# Trepanat_Pressure.net
KiCad netlist of a schematic drawn in Altium Designer
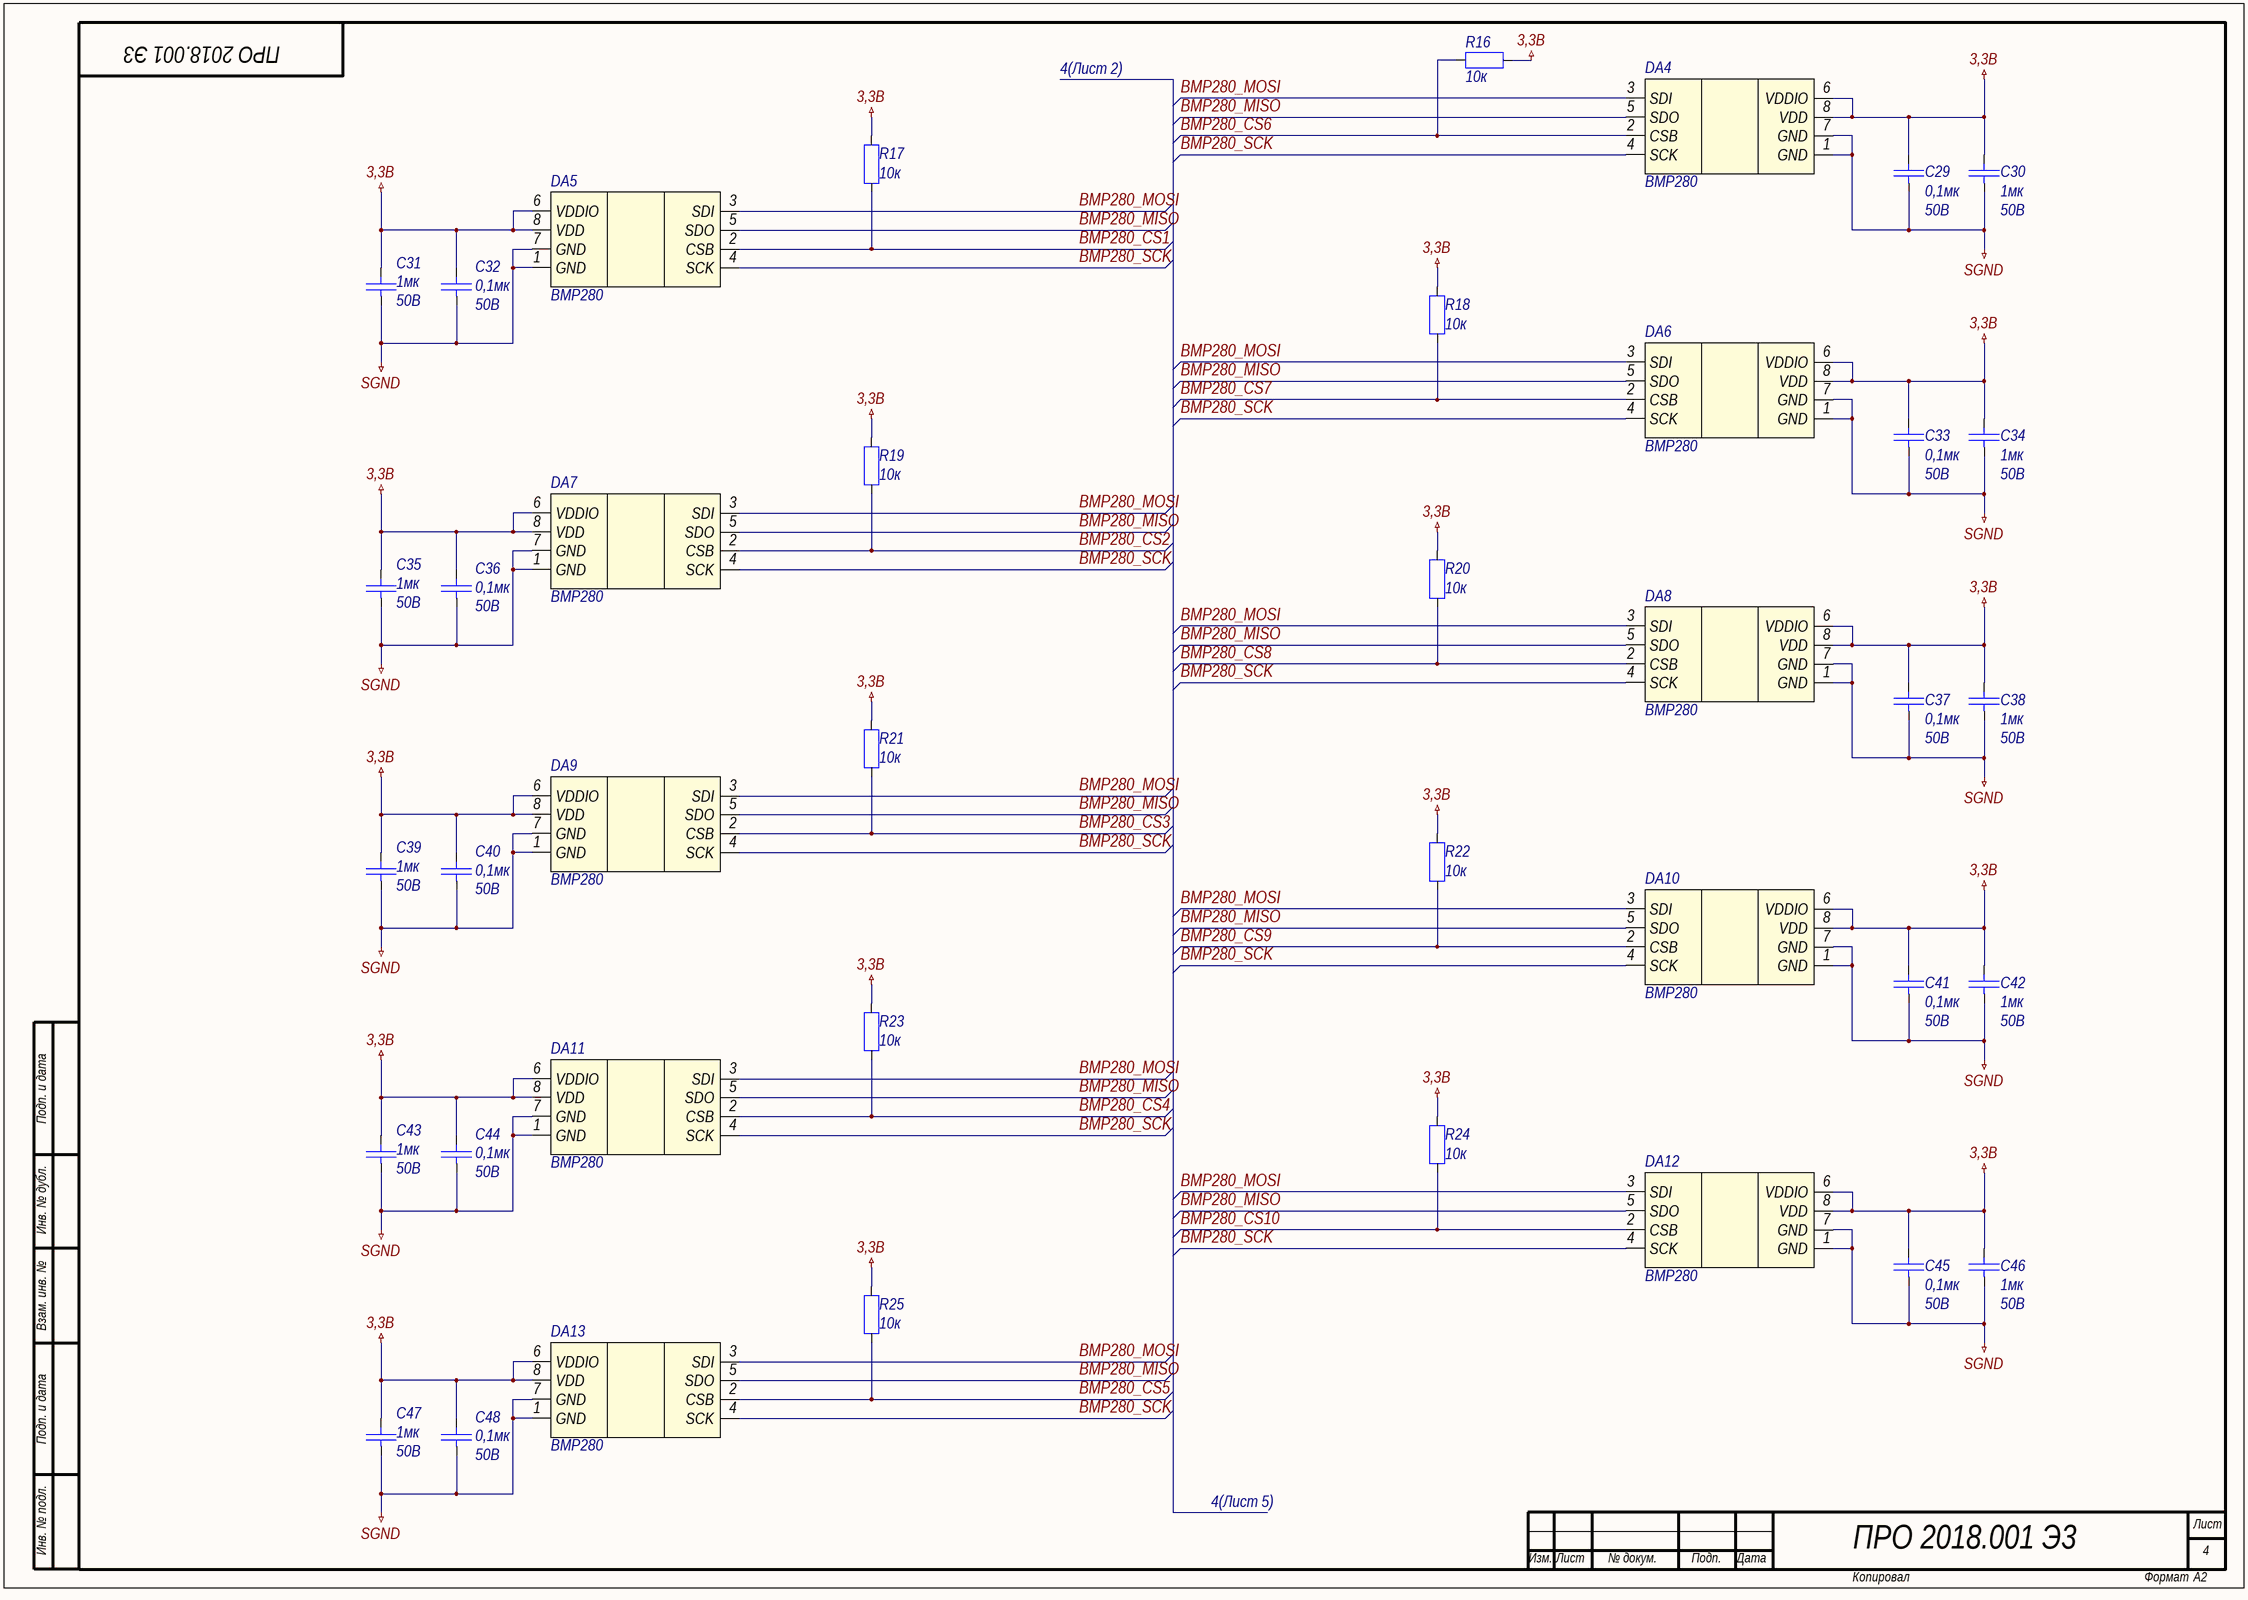
[diagram p0: Trepanat_Pressure.SchDoc]

(export (version "E")
  (design (tool "Eeschema 10.0.6"))
  (components
    (comp (ref "C29")
      (value "0,1мк")
      (footprint "ZabugorLib:C0805")
      (description "Конденсатор")
      (fields (field (name "VOLTAGE") "50В"))
      (libsource (lib "ZabugorLib") (part "Capacitor"))
    )
    (comp (ref "C30")
      (value "1мк")
      (footprint "ZabugorLib:C0805")
      (description "Конденсатор")
      (fields (field (name "VOLTAGE") "50В"))
      (libsource (lib "ZabugorLib") (part "Capacitor"))
    )
    (comp (ref "C31")
      (value "1мк")
      (footprint "ZabugorLib:C0805")
      (description "Конденсатор")
      (fields (field (name "VOLTAGE") "50В"))
      (libsource (lib "ZabugorLib") (part "Capacitor"))
    )
    (comp (ref "C32")
      (value "0,1мк")
      (footprint "ZabugorLib:C0805")
      (description "Конденсатор")
      (fields (field (name "VOLTAGE") "50В"))
      (libsource (lib "ZabugorLib") (part "Capacitor"))
    )
    (comp (ref "C33")
      (value "0,1мк")
      (footprint "ZabugorLib:C0805")
      (description "Конденсатор")
      (fields (field (name "VOLTAGE") "50В"))
      (libsource (lib "ZabugorLib") (part "Capacitor"))
    )
    (comp (ref "C34")
      (value "1мк")
      (footprint "ZabugorLib:C0805")
      (description "Конденсатор")
      (fields (field (name "VOLTAGE") "50В"))
      (libsource (lib "ZabugorLib") (part "Capacitor"))
    )
    (comp (ref "C35")
      (value "1мк")
      (footprint "ZabugorLib:C0805")
      (description "Конденсатор")
      (fields (field (name "VOLTAGE") "50В"))
      (libsource (lib "ZabugorLib") (part "Capacitor"))
    )
    (comp (ref "C36")
      (value "0,1мк")
      (footprint "ZabugorLib:C0805")
      (description "Конденсатор")
      (fields (field (name "VOLTAGE") "50В"))
      (libsource (lib "ZabugorLib") (part "Capacitor"))
    )
    (comp (ref "C37")
      (value "0,1мк")
      (footprint "ZabugorLib:C0805")
      (description "Конденсатор")
      (fields (field (name "VOLTAGE") "50В"))
      (libsource (lib "ZabugorLib") (part "Capacitor"))
    )
    (comp (ref "C38")
      (value "1мк")
      (footprint "ZabugorLib:C0805")
      (description "Конденсатор")
      (fields (field (name "VOLTAGE") "50В"))
      (libsource (lib "ZabugorLib") (part "Capacitor"))
    )
    (comp (ref "C39")
      (value "1мк")
      (footprint "ZabugorLib:C0805")
      (description "Конденсатор")
      (fields (field (name "VOLTAGE") "50В"))
      (libsource (lib "ZabugorLib") (part "Capacitor"))
    )
    (comp (ref "C40")
      (value "0,1мк")
      (footprint "ZabugorLib:C0805")
      (description "Конденсатор")
      (fields (field (name "VOLTAGE") "50В"))
      (libsource (lib "ZabugorLib") (part "Capacitor"))
    )
    (comp (ref "C41")
      (value "0,1мк")
      (footprint "ZabugorLib:C0805")
      (description "Конденсатор")
      (fields (field (name "VOLTAGE") "50В"))
      (libsource (lib "ZabugorLib") (part "Capacitor"))
    )
    (comp (ref "C42")
      (value "1мк")
      (footprint "ZabugorLib:C0805")
      (description "Конденсатор")
      (fields (field (name "VOLTAGE") "50В"))
      (libsource (lib "ZabugorLib") (part "Capacitor"))
    )
    (comp (ref "C43")
      (value "1мк")
      (footprint "ZabugorLib:C0805")
      (description "Конденсатор")
      (fields (field (name "VOLTAGE") "50В"))
      (libsource (lib "ZabugorLib") (part "Capacitor"))
    )
    (comp (ref "C44")
      (value "0,1мк")
      (footprint "ZabugorLib:C0805")
      (description "Конденсатор")
      (fields (field (name "VOLTAGE") "50В"))
      (libsource (lib "ZabugorLib") (part "Capacitor"))
    )
    (comp (ref "C45")
      (value "0,1мк")
      (footprint "ZabugorLib:C0805")
      (description "Конденсатор")
      (fields (field (name "VOLTAGE") "50В"))
      (libsource (lib "ZabugorLib") (part "Capacitor"))
    )
    (comp (ref "C46")
      (value "1мк")
      (footprint "ZabugorLib:C0805")
      (description "Конденсатор")
      (fields (field (name "VOLTAGE") "50В"))
      (libsource (lib "ZabugorLib") (part "Capacitor"))
    )
    (comp (ref "C47")
      (value "1мк")
      (footprint "ZabugorLib:C0805")
      (description "Конденсатор")
      (fields (field (name "VOLTAGE") "50В"))
      (libsource (lib "ZabugorLib") (part "Capacitor"))
    )
    (comp (ref "C48")
      (value "0,1мк")
      (footprint "ZabugorLib:C0805")
      (description "Конденсатор")
      (fields (field (name "VOLTAGE") "50В"))
      (libsource (lib "ZabugorLib") (part "Capacitor"))
    )
    (comp (ref "DA4")
      (value "BMP280")
      (footprint "ZabugorLib:BMP280")
      (description "BMP280 Barometric Sensor")
      (libsource (lib "") (part "BMP280_1"))
    )
    (comp (ref "DA5")
      (value "BMP280")
      (footprint "ZabugorLib:BMP280")
      (description "BMP280 Barometric Sensor")
      (libsource (lib "ZabugorLib") (part "BMP280"))
    )
    (comp (ref "DA6")
      (value "BMP280")
      (footprint "ZabugorLib:BMP280")
      (description "BMP280 Barometric Sensor")
      (libsource (lib "") (part "BMP280_1"))
    )
    (comp (ref "DA7")
      (value "BMP280")
      (footprint "ZabugorLib:BMP280")
      (description "BMP280 Barometric Sensor")
      (libsource (lib "ZabugorLib") (part "BMP280"))
    )
    (comp (ref "DA8")
      (value "BMP280")
      (footprint "ZabugorLib:BMP280")
      (description "BMP280 Barometric Sensor")
      (libsource (lib "") (part "BMP280_1"))
    )
    (comp (ref "DA9")
      (value "BMP280")
      (footprint "ZabugorLib:BMP280")
      (description "BMP280 Barometric Sensor")
      (libsource (lib "ZabugorLib") (part "BMP280"))
    )
    (comp (ref "DA10")
      (value "BMP280")
      (footprint "ZabugorLib:BMP280")
      (description "BMP280 Barometric Sensor")
      (libsource (lib "") (part "BMP280_1"))
    )
    (comp (ref "DA11")
      (value "BMP280")
      (footprint "ZabugorLib:BMP280")
      (description "BMP280 Barometric Sensor")
      (libsource (lib "ZabugorLib") (part "BMP280"))
    )
    (comp (ref "DA12")
      (value "BMP280")
      (footprint "ZabugorLib:BMP280")
      (description "BMP280 Barometric Sensor")
      (libsource (lib "") (part "BMP280_1"))
    )
    (comp (ref "DA13")
      (value "BMP280")
      (footprint "ZabugorLib:BMP280")
      (description "BMP280 Barometric Sensor")
      (libsource (lib "ZabugorLib") (part "BMP280"))
    )
    (comp (ref "R16")
      (value "10к")
      (footprint "ZabugorLib:R0805")
      (description "Резистор")
      (libsource (lib "") (part "Resistor_1"))
    )
    (comp (ref "R17")
      (value "10к")
      (footprint "ZabugorLib:R0805")
      (description "Резистор")
      (libsource (lib "ZabugorLib") (part "Resistor"))
    )
    (comp (ref "R18")
      (value "10к")
      (footprint "ZabugorLib:R0805")
      (description "Резистор")
      (libsource (lib "ZabugorLib") (part "Resistor"))
    )
    (comp (ref "R19")
      (value "10к")
      (footprint "ZabugorLib:R0805")
      (description "Резистор")
      (libsource (lib "ZabugorLib") (part "Resistor"))
    )
    (comp (ref "R20")
      (value "10к")
      (footprint "ZabugorLib:R0805")
      (description "Резистор")
      (libsource (lib "ZabugorLib") (part "Resistor"))
    )
    (comp (ref "R21")
      (value "10к")
      (footprint "ZabugorLib:R0805")
      (description "Резистор")
      (libsource (lib "ZabugorLib") (part "Resistor"))
    )
    (comp (ref "R22")
      (value "10к")
      (footprint "ZabugorLib:R0805")
      (description "Резистор")
      (libsource (lib "ZabugorLib") (part "Resistor"))
    )
    (comp (ref "R23")
      (value "10к")
      (footprint "ZabugorLib:R0805")
      (description "Резистор")
      (libsource (lib "ZabugorLib") (part "Resistor"))
    )
    (comp (ref "R24")
      (value "10к")
      (footprint "ZabugorLib:R0805")
      (description "Резистор")
      (libsource (lib "ZabugorLib") (part "Resistor"))
    )
    (comp (ref "R25")
      (value "10к")
      (footprint "ZabugorLib:R0805")
      (description "Резистор")
      (libsource (lib "ZabugorLib") (part "Resistor"))
    )
  )
  (nets
    (net (code "1") (name "/BMP280_CS1") (class "Default")
      (node (ref "DA5") (pin "2") (pinfunction "CSB_2") (pintype "power_in"))
      (node (ref "R17") (pin "2") (pinfunction "2_2") (pintype "passive"))
    )
    (net (code "2") (name "/BMP280_CS2") (class "Default")
      (node (ref "DA7") (pin "2") (pinfunction "CSB_2") (pintype "power_in"))
      (node (ref "R19") (pin "2") (pinfunction "2_2") (pintype "passive"))
    )
    (net (code "3") (name "/BMP280_CS3") (class "Default")
      (node (ref "DA9") (pin "2") (pinfunction "CSB_2") (pintype "power_in"))
      (node (ref "R21") (pin "2") (pinfunction "2_2") (pintype "passive"))
    )
    (net (code "4") (name "/BMP280_CS4") (class "Default")
      (node (ref "DA11") (pin "2") (pinfunction "CSB_2") (pintype "power_in"))
      (node (ref "R23") (pin "2") (pinfunction "2_2") (pintype "passive"))
    )
    (net (code "5") (name "/BMP280_CS5") (class "Default")
      (node (ref "DA13") (pin "2") (pinfunction "CSB_2") (pintype "power_in"))
      (node (ref "R25") (pin "2") (pinfunction "2_2") (pintype "passive"))
    )
    (net (code "6") (name "/BMP280_CS6") (class "Default")
      (node (ref "DA4") (pin "2") (pinfunction "CSB_2") (pintype "power_in"))
      (node (ref "R16") (pin "2") (pinfunction "2_2") (pintype "passive"))
    )
    (net (code "7") (name "/BMP280_CS7") (class "Default")
      (node (ref "DA6") (pin "2") (pinfunction "CSB_2") (pintype "power_in"))
      (node (ref "R18") (pin "2") (pinfunction "2_2") (pintype "passive"))
    )
    (net (code "8") (name "/BMP280_CS8") (class "Default")
      (node (ref "DA8") (pin "2") (pinfunction "CSB_2") (pintype "power_in"))
      (node (ref "R20") (pin "2") (pinfunction "2_2") (pintype "passive"))
    )
    (net (code "9") (name "/BMP280_CS9") (class "Default")
      (node (ref "DA10") (pin "2") (pinfunction "CSB_2") (pintype "power_in"))
      (node (ref "R22") (pin "2") (pinfunction "2_2") (pintype "passive"))
    )
    (net (code "10") (name "/BMP280_CS10") (class "Default")
      (node (ref "DA12") (pin "2") (pinfunction "CSB_2") (pintype "power_in"))
      (node (ref "R24") (pin "2") (pinfunction "2_2") (pintype "passive"))
    )
    (net (code "11") (name "/BMP280_MISO") (class "Default")
      (node (ref "DA10") (pin "5") (pinfunction "SDO_5") (pintype "power_in"))
      (node (ref "DA11") (pin "5") (pinfunction "SDO_5") (pintype "power_in"))
      (node (ref "DA12") (pin "5") (pinfunction "SDO_5") (pintype "power_in"))
      (node (ref "DA13") (pin "5") (pinfunction "SDO_5") (pintype "power_in"))
      (node (ref "DA4") (pin "5") (pinfunction "SDO_5") (pintype "power_in"))
      (node (ref "DA5") (pin "5") (pinfunction "SDO_5") (pintype "power_in"))
      (node (ref "DA6") (pin "5") (pinfunction "SDO_5") (pintype "power_in"))
      (node (ref "DA7") (pin "5") (pinfunction "SDO_5") (pintype "power_in"))
      (node (ref "DA8") (pin "5") (pinfunction "SDO_5") (pintype "power_in"))
      (node (ref "DA9") (pin "5") (pinfunction "SDO_5") (pintype "power_in"))
    )
    (net (code "12") (name "/BMP280_MOSI") (class "Default")
      (node (ref "DA10") (pin "3") (pinfunction "SDI_3") (pintype "power_in"))
      (node (ref "DA11") (pin "3") (pinfunction "SDI_3") (pintype "power_in"))
      (node (ref "DA12") (pin "3") (pinfunction "SDI_3") (pintype "power_in"))
      (node (ref "DA13") (pin "3") (pinfunction "SDI_3") (pintype "power_in"))
      (node (ref "DA4") (pin "3") (pinfunction "SDI_3") (pintype "power_in"))
      (node (ref "DA5") (pin "3") (pinfunction "SDI_3") (pintype "power_in"))
      (node (ref "DA6") (pin "3") (pinfunction "SDI_3") (pintype "power_in"))
      (node (ref "DA7") (pin "3") (pinfunction "SDI_3") (pintype "power_in"))
      (node (ref "DA8") (pin "3") (pinfunction "SDI_3") (pintype "power_in"))
      (node (ref "DA9") (pin "3") (pinfunction "SDI_3") (pintype "power_in"))
    )
    (net (code "13") (name "/BMP280_SCK") (class "Default")
      (node (ref "DA10") (pin "4") (pinfunction "SCK_4") (pintype "power_in"))
      (node (ref "DA11") (pin "4") (pinfunction "SCK_4") (pintype "power_in"))
      (node (ref "DA12") (pin "4") (pinfunction "SCK_4") (pintype "power_in"))
      (node (ref "DA13") (pin "4") (pinfunction "SCK_4") (pintype "power_in"))
      (node (ref "DA4") (pin "4") (pinfunction "SCK_4") (pintype "power_in"))
      (node (ref "DA5") (pin "4") (pinfunction "SCK_4") (pintype "power_in"))
      (node (ref "DA6") (pin "4") (pinfunction "SCK_4") (pintype "power_in"))
      (node (ref "DA7") (pin "4") (pinfunction "SCK_4") (pintype "power_in"))
      (node (ref "DA8") (pin "4") (pinfunction "SCK_4") (pintype "power_in"))
      (node (ref "DA9") (pin "4") (pinfunction "SCK_4") (pintype "power_in"))
    )
    (net (code "14") (name "3,3B") (class "Default")
      (node (ref "C29") (pin "2") (pinfunction "2_2") (pintype "passive"))
      (node (ref "C30") (pin "2") (pinfunction "2_2") (pintype "passive"))
      (node (ref "C31") (pin "2") (pinfunction "2_2") (pintype "passive"))
      (node (ref "C32") (pin "2") (pinfunction "2_2") (pintype "passive"))
      (node (ref "C33") (pin "2") (pinfunction "2_2") (pintype "passive"))
      (node (ref "C34") (pin "2") (pinfunction "2_2") (pintype "passive"))
      (node (ref "C35") (pin "2") (pinfunction "2_2") (pintype "passive"))
      (node (ref "C36") (pin "2") (pinfunction "2_2") (pintype "passive"))
      (node (ref "C37") (pin "2") (pinfunction "2_2") (pintype "passive"))
      (node (ref "C38") (pin "2") (pinfunction "2_2") (pintype "passive"))
      (node (ref "C39") (pin "2") (pinfunction "2_2") (pintype "passive"))
      (node (ref "C40") (pin "2") (pinfunction "2_2") (pintype "passive"))
      (node (ref "C41") (pin "2") (pinfunction "2_2") (pintype "passive"))
      (node (ref "C42") (pin "2") (pinfunction "2_2") (pintype "passive"))
      (node (ref "C43") (pin "2") (pinfunction "2_2") (pintype "passive"))
      (node (ref "C44") (pin "2") (pinfunction "2_2") (pintype "passive"))
      (node (ref "C45") (pin "2") (pinfunction "2_2") (pintype "passive"))
      (node (ref "C46") (pin "2") (pinfunction "2_2") (pintype "passive"))
      (node (ref "C47") (pin "2") (pinfunction "2_2") (pintype "passive"))
      (node (ref "C48") (pin "2") (pinfunction "2_2") (pintype "passive"))
      (node (ref "DA10") (pin "6") (pinfunction "VDDIO_6") (pintype "power_in"))
      (node (ref "DA10") (pin "8") (pinfunction "VDD_8") (pintype "power_in"))
      (node (ref "DA11") (pin "6") (pinfunction "VDDIO_6") (pintype "power_in"))
      (node (ref "DA11") (pin "8") (pinfunction "VDD_8") (pintype "power_in"))
      (node (ref "DA12") (pin "6") (pinfunction "VDDIO_6") (pintype "power_in"))
      (node (ref "DA12") (pin "8") (pinfunction "VDD_8") (pintype "power_in"))
      (node (ref "DA13") (pin "6") (pinfunction "VDDIO_6") (pintype "power_in"))
      (node (ref "DA13") (pin "8") (pinfunction "VDD_8") (pintype "power_in"))
      (node (ref "DA4") (pin "6") (pinfunction "VDDIO_6") (pintype "power_in"))
      (node (ref "DA4") (pin "8") (pinfunction "VDD_8") (pintype "power_in"))
      (node (ref "DA5") (pin "6") (pinfunction "VDDIO_6") (pintype "power_in"))
      (node (ref "DA5") (pin "8") (pinfunction "VDD_8") (pintype "power_in"))
      (node (ref "DA6") (pin "6") (pinfunction "VDDIO_6") (pintype "power_in"))
      (node (ref "DA6") (pin "8") (pinfunction "VDD_8") (pintype "power_in"))
      (node (ref "DA7") (pin "6") (pinfunction "VDDIO_6") (pintype "power_in"))
      (node (ref "DA7") (pin "8") (pinfunction "VDD_8") (pintype "power_in"))
      (node (ref "DA8") (pin "6") (pinfunction "VDDIO_6") (pintype "power_in"))
      (node (ref "DA8") (pin "8") (pinfunction "VDD_8") (pintype "power_in"))
      (node (ref "DA9") (pin "6") (pinfunction "VDDIO_6") (pintype "power_in"))
      (node (ref "DA9") (pin "8") (pinfunction "VDD_8") (pintype "power_in"))
      (node (ref "R16") (pin "1") (pinfunction "1_1") (pintype "passive"))
      (node (ref "R17") (pin "1") (pinfunction "1_1") (pintype "passive"))
      (node (ref "R18") (pin "1") (pinfunction "1_1") (pintype "passive"))
      (node (ref "R19") (pin "1") (pinfunction "1_1") (pintype "passive"))
      (node (ref "R20") (pin "1") (pinfunction "1_1") (pintype "passive"))
      (node (ref "R21") (pin "1") (pinfunction "1_1") (pintype "passive"))
      (node (ref "R22") (pin "1") (pinfunction "1_1") (pintype "passive"))
      (node (ref "R23") (pin "1") (pinfunction "1_1") (pintype "passive"))
      (node (ref "R24") (pin "1") (pinfunction "1_1") (pintype "passive"))
      (node (ref "R25") (pin "1") (pinfunction "1_1") (pintype "passive"))
    )
    (net (code "15") (name "SGND") (class "Default")
      (node (ref "C29") (pin "1") (pinfunction "1_1") (pintype "passive"))
      (node (ref "C30") (pin "1") (pinfunction "1_1") (pintype "passive"))
      (node (ref "C31") (pin "1") (pinfunction "1_1") (pintype "passive"))
      (node (ref "C32") (pin "1") (pinfunction "1_1") (pintype "passive"))
      (node (ref "C33") (pin "1") (pinfunction "1_1") (pintype "passive"))
      (node (ref "C34") (pin "1") (pinfunction "1_1") (pintype "passive"))
      (node (ref "C35") (pin "1") (pinfunction "1_1") (pintype "passive"))
      (node (ref "C36") (pin "1") (pinfunction "1_1") (pintype "passive"))
      (node (ref "C37") (pin "1") (pinfunction "1_1") (pintype "passive"))
      (node (ref "C38") (pin "1") (pinfunction "1_1") (pintype "passive"))
      (node (ref "C39") (pin "1") (pinfunction "1_1") (pintype "passive"))
      (node (ref "C40") (pin "1") (pinfunction "1_1") (pintype "passive"))
      (node (ref "C41") (pin "1") (pinfunction "1_1") (pintype "passive"))
      (node (ref "C42") (pin "1") (pinfunction "1_1") (pintype "passive"))
      (node (ref "C43") (pin "1") (pinfunction "1_1") (pintype "passive"))
      (node (ref "C44") (pin "1") (pinfunction "1_1") (pintype "passive"))
      (node (ref "C45") (pin "1") (pinfunction "1_1") (pintype "passive"))
      (node (ref "C46") (pin "1") (pinfunction "1_1") (pintype "passive"))
      (node (ref "C47") (pin "1") (pinfunction "1_1") (pintype "passive"))
      (node (ref "C48") (pin "1") (pinfunction "1_1") (pintype "passive"))
      (node (ref "DA10") (pin "1") (pinfunction "GND_1") (pintype "power_in"))
      (node (ref "DA10") (pin "7") (pinfunction "GND_7") (pintype "power_in"))
      (node (ref "DA11") (pin "1") (pinfunction "GND_1") (pintype "power_in"))
      (node (ref "DA11") (pin "7") (pinfunction "GND_7") (pintype "power_in"))
      (node (ref "DA12") (pin "1") (pinfunction "GND_1") (pintype "power_in"))
      (node (ref "DA12") (pin "7") (pinfunction "GND_7") (pintype "power_in"))
      (node (ref "DA13") (pin "1") (pinfunction "GND_1") (pintype "power_in"))
      (node (ref "DA13") (pin "7") (pinfunction "GND_7") (pintype "power_in"))
      (node (ref "DA4") (pin "1") (pinfunction "GND_1") (pintype "power_in"))
      (node (ref "DA4") (pin "7") (pinfunction "GND_7") (pintype "power_in"))
      (node (ref "DA5") (pin "1") (pinfunction "GND_1") (pintype "power_in"))
      (node (ref "DA5") (pin "7") (pinfunction "GND_7") (pintype "power_in"))
      (node (ref "DA6") (pin "1") (pinfunction "GND_1") (pintype "power_in"))
      (node (ref "DA6") (pin "7") (pinfunction "GND_7") (pintype "power_in"))
      (node (ref "DA7") (pin "1") (pinfunction "GND_1") (pintype "power_in"))
      (node (ref "DA7") (pin "7") (pinfunction "GND_7") (pintype "power_in"))
      (node (ref "DA8") (pin "1") (pinfunction "GND_1") (pintype "power_in"))
      (node (ref "DA8") (pin "7") (pinfunction "GND_7") (pintype "power_in"))
      (node (ref "DA9") (pin "1") (pinfunction "GND_1") (pintype "power_in"))
      (node (ref "DA9") (pin "7") (pinfunction "GND_7") (pintype "power_in"))
    )
  )
)
